# RoboBallPCB.net
KiCad netlist of a schematic drawn in Altium Designer
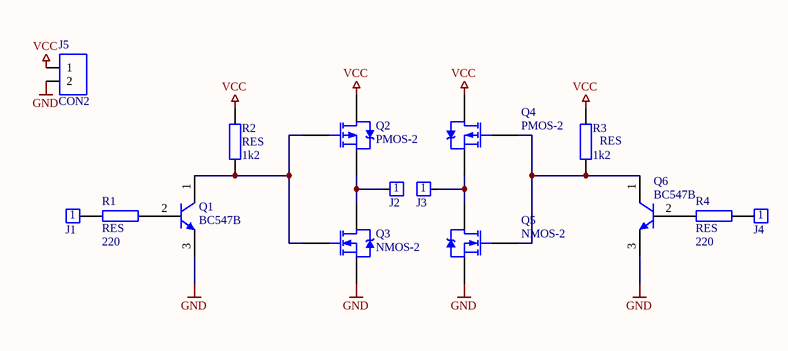
[diagram p0: RoboBallPCB.SchDoc]

(export (version "E")
  (design (tool "Eeschema 10.0.6"))
  (components
    (comp (ref "J1")
      (value "CON1")
      (footprint "Pin1")
      (description "Stecker")
      (libsource (lib "HTL-sym-2018-09") (part "CON1"))
    )
    (comp (ref "J2")
      (value "CON1")
      (footprint "Pin1")
      (description "Stecker")
      (libsource (lib "HTL-sym-2018-09") (part "CON1"))
    )
    (comp (ref "J3")
      (value "CON1")
      (footprint "Pin1")
      (description "Stecker")
      (libsource (lib "HTL-sym-2018-09") (part "CON1"))
    )
    (comp (ref "J4")
      (value "CON1")
      (footprint "Pin1")
      (description "Stecker")
      (libsource (lib "HTL-sym-2018-09") (part "CON1"))
    )
    (comp (ref "J5")
      (value "CON2")
      (footprint "SIP-2")
      (description "Stecker")
      (libsource (lib "HTL-sym-2018-02") (part "CON2"))
    )
    (comp (ref "Q1")
      (value "BC547B")
      (footprint "TO-92/EBC")
      (description "Amplifier Transistor NPN Silicon")
      (fields (field (name "PUBLISHER") "Altium Limited"))
      (libsource (lib "HTL-sym-2018-09") (part "BC546B"))
    )
    (comp (ref "Q2")
      (value "PMOS-2")
      (footprint "TO-220AB")
      (description "P-Channel Power MOSFET")
      (fields (field (name "PUBLISHER") "Altium Limited"))
      (libsource (lib "Miscellaneous Devices") (part "PMOS-2"))
    )
    (comp (ref "Q3")
      (value "NMOS-2")
      (footprint "TO-220AB")
      (description "N-Channel Power MOSFET")
      (fields (field (name "PUBLISHER") "Altium Limited"))
      (libsource (lib "Miscellaneous Devices") (part "NMOS-2"))
    )
    (comp (ref "Q4")
      (value "PMOS-2")
      (footprint "TO-220AB")
      (description "P-Channel Power MOSFET")
      (fields (field (name "PUBLISHER") "Altium Limited"))
      (libsource (lib "Miscellaneous Devices") (part "PMOS-2"))
    )
    (comp (ref "Q5")
      (value "NMOS-2")
      (footprint "TO-220AB")
      (description "N-Channel Power MOSFET")
      (fields (field (name "PUBLISHER") "Altium Limited"))
      (libsource (lib "Miscellaneous Devices") (part "NMOS-2"))
    )
    (comp (ref "Q6")
      (value "BC547B")
      (footprint "TO-92/EBC")
      (description "Amplifier Transistor NPN Silicon")
      (fields (field (name "PUBLISHER") "Altium Limited"))
      (libsource (lib "HTL-sym-2018-09") (part "BC546B"))
    )
    (comp (ref "R1")
      (value "RES")
      (footprint "Axial-0.4")
      (description "Widerstand")
      (fields (field (name "ALTIUM_VALUE") "220"))
      (libsource (lib "HTL-sym-2018-09") (part "RES"))
    )
    (comp (ref "R2")
      (value "RES")
      (footprint "Axial-0.4")
      (description "Widerstand")
      (fields (field (name "ALTIUM_VALUE") "1k2"))
      (libsource (lib "HTL-sym-2018-09") (part "RES"))
    )
    (comp (ref "R3")
      (value "RES")
      (footprint "Axial-0.4")
      (description "Widerstand")
      (fields (field (name "ALTIUM_VALUE") "1k2"))
      (libsource (lib "HTL-sym-2018-09") (part "RES"))
    )
    (comp (ref "R4")
      (value "RES")
      (footprint "Axial-0.4")
      (description "Widerstand")
      (fields (field (name "ALTIUM_VALUE") "220"))
      (libsource (lib "HTL-sym-2018-09") (part "RES"))
    )
  )
  (nets
    (net (code "1") (name "GND") (class "Default")
      (node (ref "J5") (pin "2") (pinfunction "2_2") (pintype "passive"))
      (node (ref "Q1") (pin "3") (pinfunction "E_3") (pintype "passive"))
      (node (ref "Q3") (pin "3") (pinfunction "S_3") (pintype "passive"))
      (node (ref "Q5") (pin "3") (pinfunction "S_3") (pintype "passive"))
      (node (ref "Q6") (pin "3") (pinfunction "E_3") (pintype "passive"))
    )
    (net (code "2") (name "Net-(J1-Pad1)") (class "Default")
      (node (ref "J1") (pin "1") (pinfunction "1_1") (pintype "passive"))
      (node (ref "R1") (pin "1") (pintype "passive"))
    )
    (net (code "3") (name "Net-(J4-Pad1)") (class "Default")
      (node (ref "J4") (pin "1") (pinfunction "1_1") (pintype "passive"))
      (node (ref "R4") (pin "2") (pintype "passive"))
    )
    (net (code "4") (name "Net-(Q1-B)") (class "Default")
      (node (ref "Q1") (pin "2") (pinfunction "B_2") (pintype "passive"))
      (node (ref "R1") (pin "2") (pintype "passive"))
    )
    (net (code "5") (name "Net-(Q1-C)") (class "Default")
      (node (ref "Q1") (pin "1") (pinfunction "C_1") (pintype "passive"))
      (node (ref "Q2") (pin "1") (pinfunction "G_1") (pintype "passive"))
      (node (ref "Q3") (pin "1") (pinfunction "G_1") (pintype "passive"))
      (node (ref "R2") (pin "1") (pintype "passive"))
    )
    (net (code "6") (name "Net-(Q2-S)") (class "Default")
      (node (ref "J2") (pin "1") (pinfunction "1_1") (pintype "passive"))
      (node (ref "Q2") (pin "3") (pinfunction "S_3") (pintype "passive"))
      (node (ref "Q3") (pin "2") (pinfunction "D_2") (pintype "passive"))
    )
    (net (code "7") (name "Net-(Q4-G)") (class "Default")
      (node (ref "Q4") (pin "1") (pinfunction "G_1") (pintype "passive"))
      (node (ref "Q5") (pin "1") (pinfunction "G_1") (pintype "passive"))
      (node (ref "Q6") (pin "1") (pinfunction "C_1") (pintype "passive"))
      (node (ref "R3") (pin "1") (pintype "passive"))
    )
    (net (code "8") (name "Net-(Q4-S)") (class "Default")
      (node (ref "J3") (pin "1") (pinfunction "1_1") (pintype "passive"))
      (node (ref "Q4") (pin "3") (pinfunction "S_3") (pintype "passive"))
      (node (ref "Q5") (pin "2") (pinfunction "D_2") (pintype "passive"))
    )
    (net (code "9") (name "Net-(Q6-B)") (class "Default")
      (node (ref "Q6") (pin "2") (pinfunction "B_2") (pintype "passive"))
      (node (ref "R4") (pin "1") (pintype "passive"))
    )
    (net (code "10") (name "VCC") (class "Default")
      (node (ref "J5") (pin "1") (pinfunction "1_1") (pintype "passive"))
      (node (ref "Q2") (pin "2") (pinfunction "D_2") (pintype "passive"))
      (node (ref "Q4") (pin "2") (pinfunction "D_2") (pintype "passive"))
      (node (ref "R2") (pin "2") (pintype "passive"))
      (node (ref "R3") (pin "2") (pintype "passive"))
    )
  )
)
